# Peripherals.net
KiCad netlist of a schematic drawn in Altium Designer
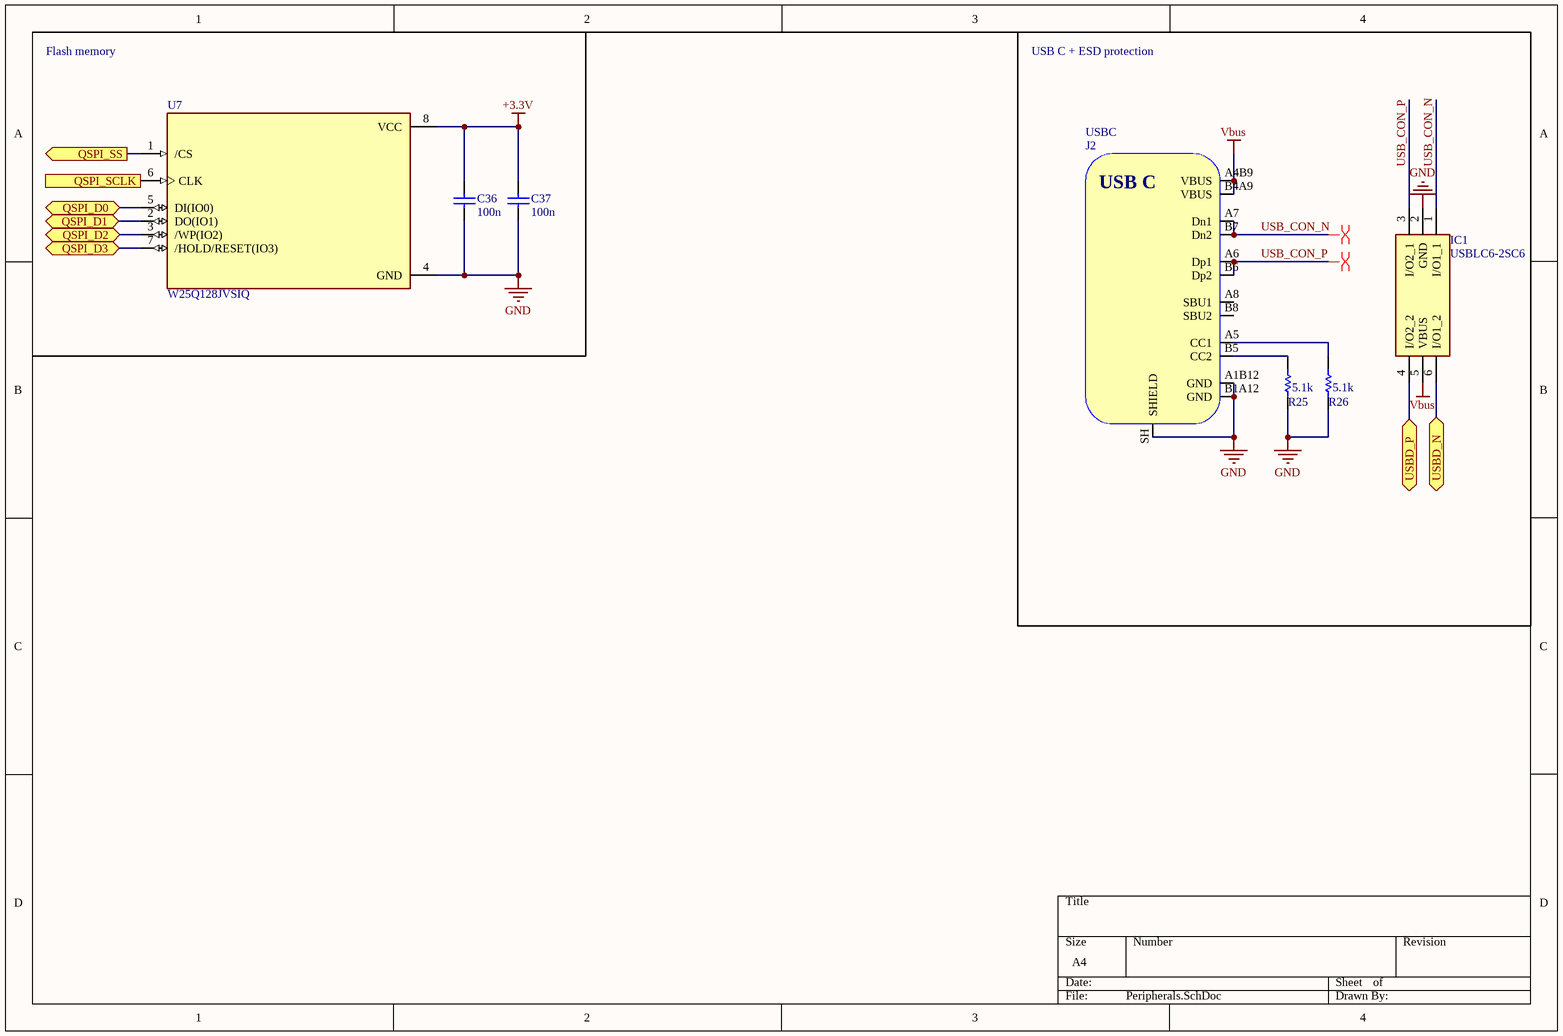
[diagram p0: Peripherals.SchDoc]

(export (version "E")
  (design (tool "Eeschema 10.0.6"))
  (components
    (comp (ref "C36")
      (value "100n")
      (footprint "RES_0805")
      (description "Capacitor")
      (libsource (lib "Simulation Generic Components") (part "Capacitor"))
    )
    (comp (ref "C37")
      (value "100n")
      (footprint "RES_0805")
      (description "Capacitor")
      (libsource (lib "Simulation Generic Components") (part "Capacitor"))
    )
    (comp (ref "IC1")
      (value "USBLC6-2SC6")
      (footprint "SamacSys:SOT95P280X145-6N")
      (description "Integrated Circuit")
      (fields (field (name "MOUSER PART NUMBER") "511-USBLC6-2SC6"))
      (libsource (lib "SamacSys") (part "USBLC6-2SC6"))
    )
    (comp (ref "J2")
      (value "USB4105-GF-A-060")
      (footprint "USB4105-GF-A-060")
      (description "USB Connector Type C SMT 12 Pin")
      (fields (field (name "MANUFACTURER") "GCT"))
      (libsource (lib "Schematic-Lib-PhilsLab") (part "USB4105-GF-A-060"))
    )
    (comp (ref "R25")
      (value "5.1k")
      (footprint "RES_0805")
      (description "Resistor")
      (libsource (lib "Simulation Generic Components") (part "Resistor"))
    )
    (comp (ref "R26")
      (value "5.1k")
      (footprint "RES_0805")
      (description "Resistor")
      (libsource (lib "Simulation Generic Components") (part "Resistor"))
    )
    (comp (ref "U7")
      (value "W25Q128JVSIQ")
      (footprint "SOIC127P790X216-8N")
      (description "FLASH - NOR Memory IC 128Mb (16M x 8) SPI - Quad I/O, QPI, DTR 133 MHz 8-SOIC")
      (fields (field (name "MF") "Winbond Electronics"))
      (libsource (lib "W25Q128JVSIQ") (part "W25Q128JVSIQ"))
    )
  )
  (nets
    (net (code "1") (name "+3.3V") (class "Default")
      (node (ref "C36") (pin "1") (pinfunction "1_1") (pintype "passive"))
      (node (ref "C37") (pin "1") (pinfunction "1_1") (pintype "passive"))
      (node (ref "U7") (pin "8") (pinfunction "VCC_8") (pintype "power_in"))
    )
    (net (code "2") (name "/QSPI_D0") (class "Default")
      (node (ref "U7") (pin "5") (pinfunction "DI(IO0)_5") (pintype "bidirectional"))
    )
    (net (code "3") (name "/QSPI_D1") (class "Default")
      (node (ref "U7") (pin "2") (pinfunction "DO(IO1)_2") (pintype "bidirectional"))
    )
    (net (code "4") (name "/QSPI_D2") (class "Default")
      (node (ref "U7") (pin "3") (pinfunction "/WP(IO2)_3") (pintype "bidirectional"))
    )
    (net (code "5") (name "/QSPI_D3") (class "Default")
      (node (ref "U7") (pin "7") (pinfunction "/HOLD/RESET(IO3)_7") (pintype "bidirectional"))
    )
    (net (code "6") (name "/QSPI_SCLK") (class "Default")
      (node (ref "U7") (pin "6") (pinfunction "CLK_6") (pintype "input"))
    )
    (net (code "7") (name "/QSPI_SS") (class "Default")
      (node (ref "U7") (pin "1") (pinfunction "/CS_1") (pintype "input"))
    )
    (net (code "8") (name "/USBD_N") (class "Default")
      (node (ref "IC1") (pin "6") (pinfunction "I/O1_2_6") (pintype "passive"))
    )
    (net (code "9") (name "/USBD_P") (class "Default")
      (node (ref "IC1") (pin "4") (pinfunction "I/O2_2_4") (pintype "passive"))
    )
    (net (code "10") (name "/USB_CON_N") (class "Default")
      (node (ref "IC1") (pin "1") (pinfunction "I/O1_1_1") (pintype "passive"))
      (node (ref "J2") (pin "A7") (pinfunction "Dn1_A7") (pintype "passive"))
      (node (ref "J2") (pin "B7") (pinfunction "Dn2_B7") (pintype "passive"))
    )
    (net (code "11") (name "/USB_CON_P") (class "Default")
      (node (ref "IC1") (pin "3") (pinfunction "I/O2_1_3") (pintype "passive"))
      (node (ref "J2") (pin "A6") (pinfunction "Dp1_A6") (pintype "passive"))
      (node (ref "J2") (pin "B6") (pinfunction "Dp2_B6") (pintype "passive"))
    )
    (net (code "12") (name "GND") (class "Default")
      (node (ref "C36") (pin "2") (pinfunction "2_2") (pintype "passive"))
      (node (ref "C37") (pin "2") (pinfunction "2_2") (pintype "passive"))
      (node (ref "IC1") (pin "2") (pinfunction "GND_2") (pintype "passive"))
      (node (ref "J2") (pin "A1B12") (pinfunction "GND_A1B12") (pintype "passive"))
      (node (ref "J2") (pin "B1A12") (pinfunction "GND_B1A12") (pintype "passive"))
      (node (ref "J2") (pin "SH") (pinfunction "SHIELD_SH") (pintype "passive"))
      (node (ref "R25") (pin "2") (pinfunction "2_2") (pintype "passive"))
      (node (ref "R26") (pin "2") (pinfunction "2_2") (pintype "passive"))
      (node (ref "U7") (pin "4") (pinfunction "GND_4") (pintype "power_in"))
    )
    (net (code "13") (name "Net-(J2-CC1)") (class "Default")
      (node (ref "J2") (pin "A5") (pinfunction "CC1_A5") (pintype "passive"))
      (node (ref "R26") (pin "1") (pinfunction "1_1") (pintype "passive"))
    )
    (net (code "14") (name "Net-(J2-CC2)") (class "Default")
      (node (ref "J2") (pin "B5") (pinfunction "CC2_B5") (pintype "passive"))
      (node (ref "R25") (pin "1") (pinfunction "1_1") (pintype "passive"))
    )
    (net (code "15") (name "Vbus") (class "Default")
      (node (ref "IC1") (pin "5") (pinfunction "VBUS_5") (pintype "passive"))
      (node (ref "J2") (pin "A4B9") (pinfunction "VBUS_A4B9") (pintype "passive"))
      (node (ref "J2") (pin "B4A9") (pinfunction "VBUS_B4A9") (pintype "passive"))
    )
    (net (code "16") (name "unconnected-(J2-SBU1-PadA8)") (class "Default")
      (node (ref "J2") (pin "A8") (pinfunction "SBU1_A8") (pintype "passive"))
    )
    (net (code "17") (name "unconnected-(J2-SBU2-PadB8)") (class "Default")
      (node (ref "J2") (pin "B8") (pinfunction "SBU2_B8") (pintype "passive"))
    )
  )
)
